# Opamp.net
KiCad netlist of a schematic drawn in Altium Designer
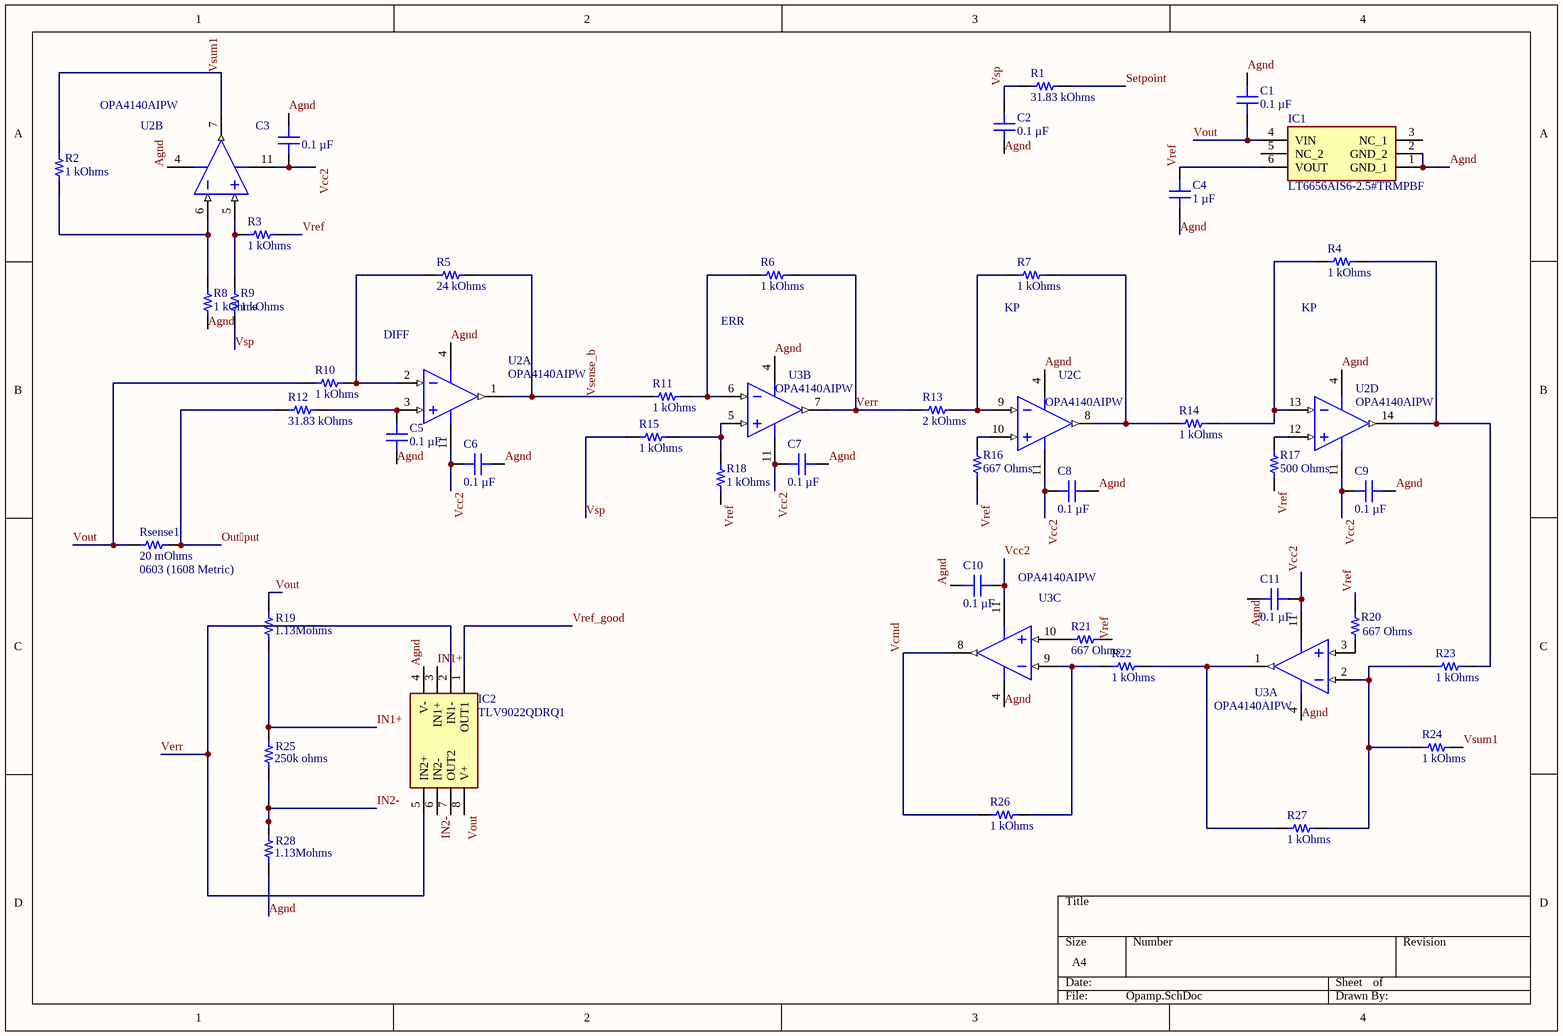
[diagram p0: Opamp.SchDoc]

(export (version "E")
  (design (tool "Eeschema 10.0.6"))
  (components
    (comp (ref "C1")
      (value "0.1 µF")
      (footprint "CAP 0603_1608")
      (description "CAP CER 0.1UF 50V X7R 0603")
      (fields (field (name "PART NUMBER") "C0603C104K5RAC7411") (field (name "MANUFACTURER") "KEMET"))
      (libsource (lib "Celestial Altium Library - altium_library") (part "Capacitor"))
    )
    (comp (ref "C2")
      (value "0.1 µF")
      (footprint "CAP 0603_1608")
      (description "CAP CER 0.1UF 50V X7R 0603")
      (fields (field (name "PART NUMBER") "C0603C104K5RAC7411") (field (name "MANUFACTURER") "KEMET"))
      (libsource (lib "Celestial Altium Library - altium_library") (part "Capacitor"))
    )
    (comp (ref "C3")
      (value "0.1 µF")
      (footprint "CAP 0603_1608")
      (description "CAP CER 0.1UF 50V X7R 0603")
      (fields (field (name "PART NUMBER") "C0603C104K5RAC7411") (field (name "MANUFACTURER") "KEMET"))
      (libsource (lib "Celestial Altium Library - altium_library") (part "Capacitor"))
    )
    (comp (ref "C4")
      (value "1 µF")
      (footprint "CAP 0603_1608")
      (description "CAP CER 1UF 16V X7R 0603")
      (fields (field (name "PART NUMBER") "C0603C105K4RACAUTO") (field (name "MANUFACTURER") "KEMET"))
      (libsource (lib "Celestial Altium Library - altium_library") (part "Capacitor"))
    )
    (comp (ref "C5")
      (value "0.1 µF")
      (footprint "CAP 0603_1608")
      (description "CAP CER 0.1UF 50V X7R 0603")
      (fields (field (name "PART NUMBER") "C0603C104K5RAC7411") (field (name "MANUFACTURER") "KEMET"))
      (libsource (lib "Celestial Altium Library - altium_library") (part "Capacitor"))
    )
    (comp (ref "C6")
      (value "0.1 µF")
      (footprint "CAP 0603_1608")
      (description "CAP CER 0.1UF 50V X7R 0603")
      (fields (field (name "PART NUMBER") "C0603C104K5RAC7411") (field (name "MANUFACTURER") "KEMET"))
      (libsource (lib "Celestial Altium Library - altium_library") (part "Capacitor"))
    )
    (comp (ref "C7")
      (value "0.1 µF")
      (footprint "CAP 0603_1608")
      (description "CAP CER 0.1UF 50V X7R 0603")
      (fields (field (name "PART NUMBER") "C0603C104K5RAC7411") (field (name "MANUFACTURER") "KEMET"))
      (libsource (lib "Celestial Altium Library - altium_library") (part "Capacitor"))
    )
    (comp (ref "C8")
      (value "0.1 µF")
      (footprint "CAP 0603_1608")
      (description "CAP CER 0.1UF 50V X7R 0603")
      (fields (field (name "PART NUMBER") "C0603C104K5RAC7411") (field (name "MANUFACTURER") "KEMET"))
      (libsource (lib "Celestial Altium Library - altium_library") (part "Capacitor"))
    )
    (comp (ref "C9")
      (value "0.1 µF")
      (footprint "CAP 0603_1608")
      (description "CAP CER 0.1UF 50V X7R 0603")
      (fields (field (name "PART NUMBER") "C0603C104K5RAC7411") (field (name "MANUFACTURER") "KEMET"))
      (libsource (lib "Celestial Altium Library - altium_library") (part "Capacitor"))
    )
    (comp (ref "C10")
      (value "0.1 µF")
      (footprint "CAP 0603_1608")
      (description "CAP CER 0.1UF 50V X7R 0603")
      (fields (field (name "PART NUMBER") "C0603C104K5RAC7411") (field (name "MANUFACTURER") "KEMET"))
      (libsource (lib "Celestial Altium Library - altium_library") (part "Capacitor"))
    )
    (comp (ref "C11")
      (value "0.1 µF")
      (footprint "CAP 0603_1608")
      (description "CAP CER 0.1UF 50V X7R 0603")
      (fields (field (name "PART NUMBER") "C0603C104K5RAC7411") (field (name "MANUFACTURER") "KEMET"))
      (libsource (lib "Celestial Altium Library - altium_library") (part "Capacitor"))
    )
    (comp (ref "IC1")
      (value "LT6656AIS6-2.5#TRMPBF")
      (footprint "SamacSys:SOT95P280X100-6N")
      (description "Integrated Circuit")
      (fields (field (name "MOUSER PART NUMBER") "584-6656AIS6-2.5TMPF"))
      (libsource (lib "*") (part "LT6656AIS6-2.5#TRMPBF"))
    )
    (comp (ref "IC2")
      (value "TLV9022QDRQ1")
      (footprint "SamacSys:SOIC127P600X175-8N")
      (description "Integrated Circuit")
      (fields (field (name "MOUSER PART NUMBER") "595-TLV9022QDRQ1"))
      (libsource (lib "*") (part "TLV9022QDRQ1"))
    )
    (comp (ref "R1")
      (value "31.83 kOhms")
      (footprint "RES 0603_1608")
      (description "RES 10K OHM 0.1% 1/16W 0603")
      (fields
        (field (name "PART NUMBER") "RNCS0603BKE10K0")
        (field (name "MANUFACTURER") "Stackpole Electronics Inc")
      )
      (libsource (lib "Celestial Altium Library - altium_library") (part "Resistor"))
    )
    (comp (ref "R2")
      (value "1 kOhms")
      (footprint "RES 0603_1608")
      (description "RES 10K OHM 0.1% 1/16W 0603")
      (fields
        (field (name "PART NUMBER") "RNCS0603BKE10K0")
        (field (name "MANUFACTURER") "Stackpole Electronics Inc")
      )
      (libsource (lib "Celestial Altium Library - altium_library") (part "Resistor"))
    )
    (comp (ref "R3")
      (value "1 kOhms")
      (footprint "RES 0603_1608")
      (description "RES 10K OHM 0.1% 1/16W 0603")
      (fields
        (field (name "PART NUMBER") "RNCS0603BKE10K0")
        (field (name "MANUFACTURER") "Stackpole Electronics Inc")
      )
      (libsource (lib "Celestial Altium Library - altium_library") (part "Resistor"))
    )
    (comp (ref "R4")
      (value "1 kOhms")
      (footprint "RES 0603_1608")
      (description "RES 10K OHM 0.1% 1/16W 0603")
      (fields
        (field (name "PART NUMBER") "RNCS0603BKE10K0")
        (field (name "MANUFACTURER") "Stackpole Electronics Inc")
      )
      (libsource (lib "Celestial Altium Library - altium_library") (part "Resistor"))
    )
    (comp (ref "R5")
      (value "24 kOhms")
      (footprint "RES 0603_1608")
      (description "RES 10K OHM 0.1% 1/16W 0603")
      (fields
        (field (name "PART NUMBER") "RNCS0603BKE10K0")
        (field (name "MANUFACTURER") "Stackpole Electronics Inc")
      )
      (libsource (lib "Celestial Altium Library - altium_library") (part "Resistor"))
    )
    (comp (ref "R6")
      (value "1 kOhms")
      (footprint "RES 0603_1608")
      (description "RES 10K OHM 0.1% 1/16W 0603")
      (fields
        (field (name "PART NUMBER") "RNCS0603BKE10K0")
        (field (name "MANUFACTURER") "Stackpole Electronics Inc")
      )
      (libsource (lib "Celestial Altium Library - altium_library") (part "Resistor"))
    )
    (comp (ref "R7")
      (value "1 kOhms")
      (footprint "RES 0603_1608")
      (description "RES 10K OHM 0.1% 1/16W 0603")
      (fields
        (field (name "PART NUMBER") "RNCS0603BKE10K0")
        (field (name "MANUFACTURER") "Stackpole Electronics Inc")
      )
      (libsource (lib "Celestial Altium Library - altium_library") (part "Resistor"))
    )
    (comp (ref "R8")
      (value "1 kOhms")
      (footprint "RES 0603_1608")
      (description "RES 10K OHM 0.1% 1/16W 0603")
      (fields
        (field (name "PART NUMBER") "RNCS0603BKE10K0")
        (field (name "MANUFACTURER") "Stackpole Electronics Inc")
      )
      (libsource (lib "Celestial Altium Library - altium_library") (part "Resistor"))
    )
    (comp (ref "R9")
      (value "1 kOhms")
      (footprint "RES 0603_1608")
      (description "RES 10K OHM 0.1% 1/16W 0603")
      (fields
        (field (name "PART NUMBER") "RNCS0603BKE10K0")
        (field (name "MANUFACTURER") "Stackpole Electronics Inc")
      )
      (libsource (lib "Celestial Altium Library - altium_library") (part "Resistor"))
    )
    (comp (ref "R10")
      (value "1 kOhms")
      (footprint "RES 0603_1608")
      (description "RES 10K OHM 0.1% 1/16W 0603")
      (fields
        (field (name "PART NUMBER") "RNCS0603BKE10K0")
        (field (name "MANUFACTURER") "Stackpole Electronics Inc")
      )
      (libsource (lib "Celestial Altium Library - altium_library") (part "Resistor"))
    )
    (comp (ref "R11")
      (value "1 kOhms")
      (footprint "RES 0603_1608")
      (description "RES 10K OHM 0.1% 1/16W 0603")
      (fields
        (field (name "PART NUMBER") "RNCS0603BKE10K0")
        (field (name "MANUFACTURER") "Stackpole Electronics Inc")
      )
      (libsource (lib "Celestial Altium Library - altium_library") (part "Resistor"))
    )
    (comp (ref "R12")
      (value "31.83 kOhms")
      (footprint "RES 0603_1608")
      (description "RES 10K OHM 0.1% 1/16W 0603")
      (fields
        (field (name "PART NUMBER") "RNCS0603BKE10K0")
        (field (name "MANUFACTURER") "Stackpole Electronics Inc")
      )
      (libsource (lib "Celestial Altium Library - altium_library") (part "Resistor"))
    )
    (comp (ref "R13")
      (value "2 kOhms")
      (footprint "RES 0603_1608")
      (description "RES 10K OHM 0.1% 1/16W 0603")
      (fields
        (field (name "PART NUMBER") "RNCS0603BKE10K0")
        (field (name "MANUFACTURER") "Stackpole Electronics Inc")
      )
      (libsource (lib "Celestial Altium Library - altium_library") (part "Resistor"))
    )
    (comp (ref "R14")
      (value "1 kOhms")
      (footprint "RES 0603_1608")
      (description "RES 10K OHM 0.1% 1/16W 0603")
      (fields
        (field (name "PART NUMBER") "RNCS0603BKE10K0")
        (field (name "MANUFACTURER") "Stackpole Electronics Inc")
      )
      (libsource (lib "Celestial Altium Library - altium_library") (part "Resistor"))
    )
    (comp (ref "R15")
      (value "1 kOhms")
      (footprint "RES 0603_1608")
      (description "RES 10K OHM 0.1% 1/16W 0603")
      (fields
        (field (name "PART NUMBER") "RNCS0603BKE10K0")
        (field (name "MANUFACTURER") "Stackpole Electronics Inc")
      )
      (libsource (lib "Celestial Altium Library - altium_library") (part "Resistor"))
    )
    (comp (ref "R16")
      (value "667 Ohms")
      (footprint "RES 0603_1608")
      (description "RES 10K OHM 0.1% 1/16W 0603")
      (fields
        (field (name "PART NUMBER") "RNCS0603BKE10K0")
        (field (name "MANUFACTURER") "Stackpole Electronics Inc")
      )
      (libsource (lib "Celestial Altium Library - altium_library") (part "Resistor"))
    )
    (comp (ref "R17")
      (value "500 Ohms")
      (footprint "RES 0603_1608")
      (description "RES 10K OHM 0.1% 1/16W 0603")
      (fields
        (field (name "PART NUMBER") "RNCS0603BKE10K0")
        (field (name "MANUFACTURER") "Stackpole Electronics Inc")
      )
      (libsource (lib "Celestial Altium Library - altium_library") (part "Resistor"))
    )
    (comp (ref "R18")
      (value "1 kOhms")
      (footprint "RES 0603_1608")
      (description "RES 10K OHM 0.1% 1/16W 0603")
      (fields
        (field (name "PART NUMBER") "RNCS0603BKE10K0")
        (field (name "MANUFACTURER") "Stackpole Electronics Inc")
      )
      (libsource (lib "Celestial Altium Library - altium_library") (part "Resistor"))
    )
    (comp (ref "R19")
      (value "1.13Mohms")
      (footprint "RES 0603_1608")
      (description "RES 10K OHM 0.1% 1/16W 0603")
      (fields
        (field (name "PART NUMBER") "RNCS0603BKE10K0")
        (field (name "MANUFACTURER") "Stackpole Electronics Inc")
      )
      (libsource (lib "Celestial Altium Library - altium_library") (part "Resistor"))
    )
    (comp (ref "R20")
      (value "667 Ohms")
      (footprint "RES 0603_1608")
      (description "RES 10K OHM 0.1% 1/16W 0603")
      (fields
        (field (name "PART NUMBER") "RNCS0603BKE10K0")
        (field (name "MANUFACTURER") "Stackpole Electronics Inc")
      )
      (libsource (lib "Celestial Altium Library - altium_library") (part "Resistor"))
    )
    (comp (ref "R21")
      (value "667 Ohms")
      (footprint "RES 0603_1608")
      (description "RES 10K OHM 0.1% 1/16W 0603")
      (fields
        (field (name "PART NUMBER") "RNCS0603BKE10K0")
        (field (name "MANUFACTURER") "Stackpole Electronics Inc")
      )
      (libsource (lib "Celestial Altium Library - altium_library") (part "Resistor"))
    )
    (comp (ref "R22")
      (value "1 kOhms")
      (footprint "RES 0603_1608")
      (description "RES 10K OHM 0.1% 1/16W 0603")
      (fields
        (field (name "PART NUMBER") "RNCS0603BKE10K0")
        (field (name "MANUFACTURER") "Stackpole Electronics Inc")
      )
      (libsource (lib "Celestial Altium Library - altium_library") (part "Resistor"))
    )
    (comp (ref "R23")
      (value "1 kOhms")
      (footprint "RES 0603_1608")
      (description "RES 10K OHM 0.1% 1/16W 0603")
      (fields
        (field (name "PART NUMBER") "RNCS0603BKE10K0")
        (field (name "MANUFACTURER") "Stackpole Electronics Inc")
      )
      (libsource (lib "Celestial Altium Library - altium_library") (part "Resistor"))
    )
    (comp (ref "R24")
      (value "1 kOhms")
      (footprint "RES 0603_1608")
      (description "RES 10K OHM 0.1% 1/16W 0603")
      (fields
        (field (name "PART NUMBER") "RNCS0603BKE10K0")
        (field (name "MANUFACTURER") "Stackpole Electronics Inc")
      )
      (libsource (lib "Celestial Altium Library - altium_library") (part "Resistor"))
    )
    (comp (ref "R25")
      (value "250k ohms")
      (footprint "RES 0603_1608")
      (description "RES 10K OHM 0.1% 1/16W 0603")
      (fields
        (field (name "PART NUMBER") "RNCS0603BKE10K0")
        (field (name "MANUFACTURER") "Stackpole Electronics Inc")
      )
      (libsource (lib "Celestial Altium Library - altium_library") (part "Resistor"))
    )
    (comp (ref "R26")
      (value "1 kOhms")
      (footprint "RES 0603_1608")
      (description "RES 10K OHM 0.1% 1/16W 0603")
      (fields
        (field (name "PART NUMBER") "RNCS0603BKE10K0")
        (field (name "MANUFACTURER") "Stackpole Electronics Inc")
      )
      (libsource (lib "Celestial Altium Library - altium_library") (part "Resistor"))
    )
    (comp (ref "R27")
      (value "1 kOhms")
      (footprint "RES 0603_1608")
      (description "RES 10K OHM 0.1% 1/16W 0603")
      (fields
        (field (name "PART NUMBER") "RNCS0603BKE10K0")
        (field (name "MANUFACTURER") "Stackpole Electronics Inc")
      )
      (libsource (lib "Celestial Altium Library - altium_library") (part "Resistor"))
    )
    (comp (ref "R28")
      (value "1.13Mohms")
      (footprint "RES 0603_1608")
      (description "RES 10K OHM 0.1% 1/16W 0603")
      (fields
        (field (name "PART NUMBER") "RNCS0603BKE10K0")
        (field (name "MANUFACTURER") "Stackpole Electronics Inc")
      )
      (libsource (lib "Celestial Altium Library - altium_library") (part "Resistor"))
    )
    (comp (ref "Rsense1")
      (value "20 mOhms")
      (footprint "STACKPOLE CSR0603")
      (description "RES 0.02 OHM 1% 1/3W 0603")
      (fields
        (field (name "PART NUMBER") "LVT06R0200FER")
        (field (name "PACKAGE / CASE") "0603 (1608 Metric)")
        (field (name "MANUFACTURER") "Ohmite")
      )
      (libsource (lib "Celestial Altium Library - altium_library") (part "Resistor"))
    )
    (comp (ref "U2")
      (value "OPA4140AIPW")
      (footprint "PW0014A_L")
      (fields (field (name "MANUFACTURER") "Texas Instruments"))
      (libsource (lib "Components - 10.07.23 - 17.00") (part "CMP-0272-01663-3"))
    )
    (comp (ref "U3")
      (value "OPA4140AIPW")
      (footprint "PW0014A_L")
      (fields (field (name "MANUFACTURER") "Texas Instruments"))
      (libsource (lib "Components - 10.07.23 - 17.00") (part "CMP-0272-01663-3"))
    )
  )
  (nets
    (net (code "1") (name "/Agnd") (class "Default")
      (node (ref "C1") (pin "1") (pinfunction "1_1") (pintype "passive"))
      (node (ref "C10") (pin "1") (pinfunction "1_1") (pintype "passive"))
      (node (ref "C11") (pin "1") (pinfunction "1_1") (pintype "passive"))
      (node (ref "C2") (pin "2") (pinfunction "2_2") (pintype "passive"))
      (node (ref "C3") (pin "1") (pinfunction "1_1") (pintype "passive"))
      (node (ref "C4") (pin "2") (pinfunction "2_2") (pintype "passive"))
      (node (ref "C5") (pin "2") (pinfunction "2_2") (pintype "passive"))
      (node (ref "C6") (pin "1") (pinfunction "1_1") (pintype "passive"))
      (node (ref "C7") (pin "1") (pinfunction "1_1") (pintype "passive"))
      (node (ref "C8") (pin "1") (pinfunction "1_1") (pintype "passive"))
      (node (ref "C9") (pin "1") (pinfunction "1_1") (pintype "passive"))
      (node (ref "IC1") (pin "1") (pinfunction "GND_1_1") (pintype "passive"))
      (node (ref "IC1") (pin "2") (pinfunction "GND_2_2") (pintype "passive"))
      (node (ref "IC2") (pin "4") (pinfunction "V-_4") (pintype "passive"))
      (node (ref "R28") (pin "2") (pinfunction "2_2") (pintype "passive"))
      (node (ref "R8") (pin "2") (pinfunction "2_2") (pintype "passive"))
      (node (ref "U2") (pin "4") (pinfunction "V+_4") (pintype "power_in"))
      (node (ref "U3") (pin "4") (pinfunction "V+_4") (pintype "power_in"))
    )
    (net (code "2") (name "/IN1+") (class "Default")
      (node (ref "IC2") (pin "3") (pinfunction "IN1+_3") (pintype "passive"))
      (node (ref "R19") (pin "2") (pinfunction "2_2") (pintype "passive"))
      (node (ref "R25") (pin "1") (pinfunction "1_1") (pintype "passive"))
    )
    (net (code "3") (name "/IN2-") (class "Default")
      (node (ref "IC2") (pin "6") (pinfunction "IN2-_6") (pintype "passive"))
      (node (ref "R25") (pin "2") (pinfunction "2_2") (pintype "passive"))
      (node (ref "R28") (pin "1") (pinfunction "1_1") (pintype "passive"))
    )
    (net (code "4") (name "/Output") (class "Default")
      (node (ref "R12") (pin "2") (pinfunction "2_2") (pintype "passive"))
      (node (ref "Rsense1") (pin "1") (pinfunction "1_1") (pintype "passive"))
    )
    (net (code "5") (name "/Setpoint") (class "Default")
      (node (ref "R1") (pin "1") (pinfunction "1_1") (pintype "passive"))
    )
    (net (code "6") (name "/Vcc2") (class "Default")
      (node (ref "C10") (pin "2") (pinfunction "2_2") (pintype "passive"))
      (node (ref "C11") (pin "2") (pinfunction "2_2") (pintype "passive"))
      (node (ref "C3") (pin "2") (pinfunction "2_2") (pintype "passive"))
      (node (ref "C6") (pin "2") (pinfunction "2_2") (pintype "passive"))
      (node (ref "C7") (pin "2") (pinfunction "2_2") (pintype "passive"))
      (node (ref "C8") (pin "2") (pinfunction "2_2") (pintype "passive"))
      (node (ref "C9") (pin "2") (pinfunction "2_2") (pintype "passive"))
      (node (ref "U2") (pin "11") (pinfunction "V-_11") (pintype "power_in"))
      (node (ref "U3") (pin "11") (pinfunction "V-_11") (pintype "power_in"))
    )
    (net (code "7") (name "/Vcmd") (class "Default")
      (node (ref "R26") (pin "1") (pinfunction "1_1") (pintype "passive"))
      (node (ref "U3") (pin "8") (pinfunction "OUT_C_8") (pintype "output"))
    )
    (net (code "8") (name "/Verr") (class "Default")
      (node (ref "IC2") (pin "2") (pinfunction "IN1-_2") (pintype "passive"))
      (node (ref "IC2") (pin "5") (pinfunction "IN2+_5") (pintype "passive"))
      (node (ref "R13") (pin "2") (pinfunction "2_2") (pintype "passive"))
      (node (ref "R6") (pin "1") (pinfunction "1_1") (pintype "passive"))
      (node (ref "U3") (pin "7") (pinfunction "OUT_B_7") (pintype "output"))
    )
    (net (code "9") (name "/Vout") (class "Default")
      (node (ref "C1") (pin "2") (pinfunction "2_2") (pintype "passive"))
      (node (ref "IC1") (pin "4") (pinfunction "VIN_4") (pintype "passive"))
      (node (ref "IC2") (pin "8") (pinfunction "V+_8") (pintype "passive"))
      (node (ref "R10") (pin "2") (pinfunction "2_2") (pintype "passive"))
      (node (ref "R19") (pin "1") (pinfunction "1_1") (pintype "passive"))
      (node (ref "Rsense1") (pin "2") (pinfunction "2_2") (pintype "passive"))
    )
    (net (code "10") (name "/Vref") (class "Default")
      (node (ref "C4") (pin "1") (pinfunction "1_1") (pintype "passive"))
      (node (ref "IC1") (pin "6") (pinfunction "VOUT_6") (pintype "passive"))
      (node (ref "R16") (pin "1") (pinfunction "1_1") (pintype "passive"))
      (node (ref "R17") (pin "1") (pinfunction "1_1") (pintype "passive"))
      (node (ref "R18") (pin "2") (pinfunction "2_2") (pintype "passive"))
      (node (ref "R20") (pin "2") (pinfunction "2_2") (pintype "passive"))
      (node (ref "R21") (pin "2") (pinfunction "2_2") (pintype "passive"))
      (node (ref "R3") (pin "2") (pinfunction "2_2") (pintype "passive"))
    )
    (net (code "11") (name "/Vref_good") (class "Default")
      (node (ref "IC2") (pin "1") (pinfunction "OUT1_1") (pintype "passive"))
    )
    (net (code "12") (name "/Vsense_b") (class "Default")
      (node (ref "R11") (pin "2") (pinfunction "2_2") (pintype "passive"))
      (node (ref "R5") (pin "2") (pinfunction "2_2") (pintype "passive"))
      (node (ref "U2") (pin "1") (pinfunction "OUT_A_1") (pintype "output"))
    )
    (net (code "13") (name "/Vsp") (class "Default")
      (node (ref "C2") (pin "1") (pinfunction "1_1") (pintype "passive"))
      (node (ref "R1") (pin "2") (pinfunction "2_2") (pintype "passive"))
      (node (ref "R15") (pin "2") (pinfunction "2_2") (pintype "passive"))
      (node (ref "R9") (pin "2") (pinfunction "2_2") (pintype "passive"))
    )
    (net (code "14") (name "/Vsum1") (class "Default")
      (node (ref "R2") (pin "1") (pinfunction "1_1") (pintype "passive"))
      (node (ref "R24") (pin "2") (pinfunction "2_2") (pintype "passive"))
      (node (ref "U2") (pin "7") (pinfunction "OUT_B_7") (pintype "output"))
    )
    (net (code "15") (name "Net-(U2A-IN_A+)") (class "Default")
      (node (ref "C5") (pin "1") (pinfunction "1_1") (pintype "passive"))
      (node (ref "R12") (pin "1") (pinfunction "1_1") (pintype "passive"))
      (node (ref "U2") (pin "3") (pinfunction "IN_A+_3") (pintype "input"))
    )
    (net (code "16") (name "Net-(U2A-IN_A-)") (class "Default")
      (node (ref "R10") (pin "1") (pinfunction "1_1") (pintype "passive"))
      (node (ref "R5") (pin "1") (pinfunction "1_1") (pintype "passive"))
      (node (ref "U2") (pin "2") (pinfunction "IN_A-_2") (pintype "input"))
    )
    (net (code "17") (name "Net-(U2B-IN_B+)") (class "Default")
      (node (ref "R3") (pin "1") (pinfunction "1_1") (pintype "passive"))
      (node (ref "R9") (pin "1") (pinfunction "1_1") (pintype "passive"))
      (node (ref "U2") (pin "5") (pinfunction "IN_B+_5") (pintype "input"))
    )
    (net (code "18") (name "Net-(U2B-IN_B-)") (class "Default")
      (node (ref "R2") (pin "2") (pinfunction "2_2") (pintype "passive"))
      (node (ref "R8") (pin "1") (pinfunction "1_1") (pintype "passive"))
      (node (ref "U2") (pin "6") (pinfunction "IN_B-_6") (pintype "input"))
    )
    (net (code "19") (name "Net-(U2C-IN_C+)") (class "Default")
      (node (ref "R16") (pin "2") (pinfunction "2_2") (pintype "passive"))
      (node (ref "U2") (pin "10") (pinfunction "IN_C+_10") (pintype "input"))
    )
    (net (code "20") (name "Net-(U2C-IN_C-)") (class "Default")
      (node (ref "R13") (pin "1") (pinfunction "1_1") (pintype "passive"))
      (node (ref "R7") (pin "2") (pinfunction "2_2") (pintype "passive"))
      (node (ref "U2") (pin "9") (pinfunction "IN_C-_9") (pintype "input"))
    )
    (net (code "21") (name "Net-(U2C-OUT_C)") (class "Default")
      (node (ref "R14") (pin "2") (pinfunction "2_2") (pintype "passive"))
      (node (ref "R7") (pin "1") (pinfunction "1_1") (pintype "passive"))
      (node (ref "U2") (pin "8") (pinfunction "OUT_C_8") (pintype "output"))
    )
    (net (code "22") (name "Net-(U2D-IN_D+)") (class "Default")
      (node (ref "R17") (pin "2") (pinfunction "2_2") (pintype "passive"))
      (node (ref "U2") (pin "12") (pinfunction "IN_D+_12") (pintype "input"))
    )
    (net (code "23") (name "Net-(U2D-IN_D-)") (class "Default")
      (node (ref "R14") (pin "1") (pinfunction "1_1") (pintype "passive"))
      (node (ref "R4") (pin "2") (pinfunction "2_2") (pintype "passive"))
      (node (ref "U2") (pin "13") (pinfunction "IN_D-_13") (pintype "input"))
    )
    (net (code "24") (name "Net-(U2D-OUT_D)") (class "Default")
      (node (ref "R23") (pin "2") (pinfunction "2_2") (pintype "passive"))
      (node (ref "R4") (pin "1") (pinfunction "1_1") (pintype "passive"))
      (node (ref "U2") (pin "14") (pinfunction "OUT_D_14") (pintype "output"))
    )
    (net (code "25") (name "Net-(U3A-IN_A+)") (class "Default")
      (node (ref "R20") (pin "1") (pinfunction "1_1") (pintype "passive"))
      (node (ref "U3") (pin "3") (pinfunction "IN_A+_3") (pintype "input"))
    )
    (net (code "26") (name "Net-(U3A-IN_A-)") (class "Default")
      (node (ref "R23") (pin "1") (pinfunction "1_1") (pintype "passive"))
      (node (ref "R24") (pin "1") (pinfunction "1_1") (pintype "passive"))
      (node (ref "R27") (pin "2") (pinfunction "2_2") (pintype "passive"))
      (node (ref "U3") (pin "2") (pinfunction "IN_A-_2") (pintype "input"))
    )
    (net (code "27") (name "Net-(U3A-OUT_A)") (class "Default")
      (node (ref "R22") (pin "2") (pinfunction "2_2") (pintype "passive"))
      (node (ref "R27") (pin "1") (pinfunction "1_1") (pintype "passive"))
      (node (ref "U3") (pin "1") (pinfunction "OUT_A_1") (pintype "output"))
    )
    (net (code "28") (name "Net-(U3B-IN_B+)") (class "Default")
      (node (ref "R15") (pin "1") (pinfunction "1_1") (pintype "passive"))
      (node (ref "R18") (pin "1") (pinfunction "1_1") (pintype "passive"))
      (node (ref "U3") (pin "5") (pinfunction "IN_B+_5") (pintype "input"))
    )
    (net (code "29") (name "Net-(U3B-IN_B-)") (class "Default")
      (node (ref "R11") (pin "1") (pinfunction "1_1") (pintype "passive"))
      (node (ref "R6") (pin "2") (pinfunction "2_2") (pintype "passive"))
      (node (ref "U3") (pin "6") (pinfunction "IN_B-_6") (pintype "input"))
    )
    (net (code "30") (name "Net-(U3C-IN_C+)") (class "Default")
      (node (ref "R21") (pin "1") (pinfunction "1_1") (pintype "passive"))
      (node (ref "U3") (pin "10") (pinfunction "IN_C+_10") (pintype "input"))
    )
    (net (code "31") (name "Net-(U3C-IN_C-)") (class "Default")
      (node (ref "R22") (pin "1") (pinfunction "1_1") (pintype "passive"))
      (node (ref "R26") (pin "2") (pinfunction "2_2") (pintype "passive"))
      (node (ref "U3") (pin "9") (pinfunction "IN_C-_9") (pintype "input"))
    )
    (net (code "32") (name "unconnected-(IC1-NC_1-Pad3)") (class "Default")
      (node (ref "IC1") (pin "3") (pinfunction "NC_1_3") (pintype "passive"))
    )
    (net (code "33") (name "unconnected-(IC1-NC_2-Pad5)") (class "Default")
      (node (ref "IC1") (pin "5") (pinfunction "NC_2_5") (pintype "passive"))
    )
    (net (code "34") (name "unconnected-(IC2-OUT2-Pad7)") (class "Default")
      (node (ref "IC2") (pin "7") (pinfunction "OUT2_7") (pintype "passive"))
    )
  )
)
